# ESP_82661.net
KiCad netlist of a schematic drawn in Altium Designer
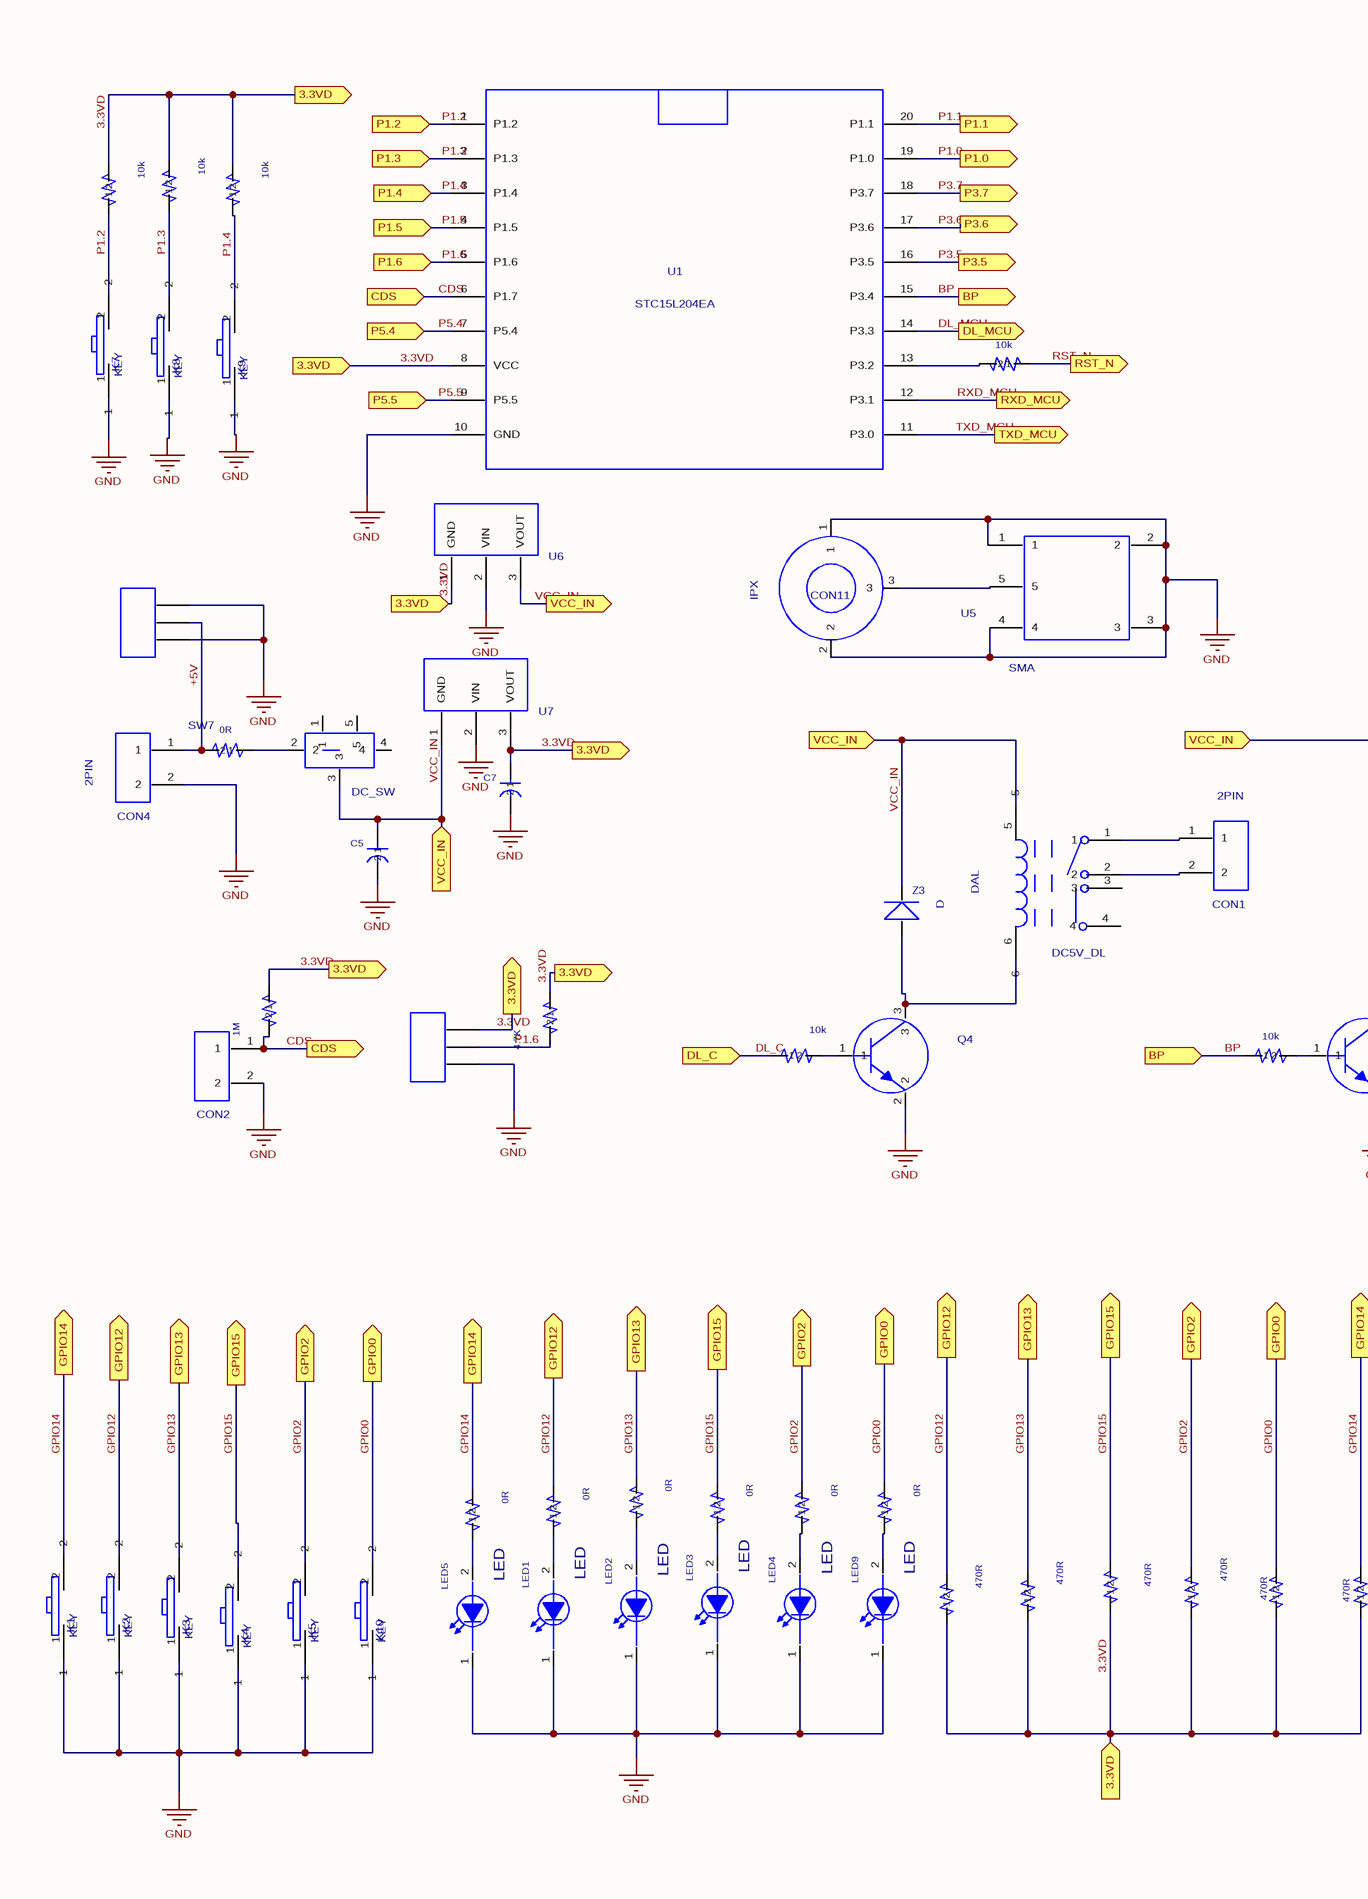
[diagram p0: ESP_82661.SchDoc, left]
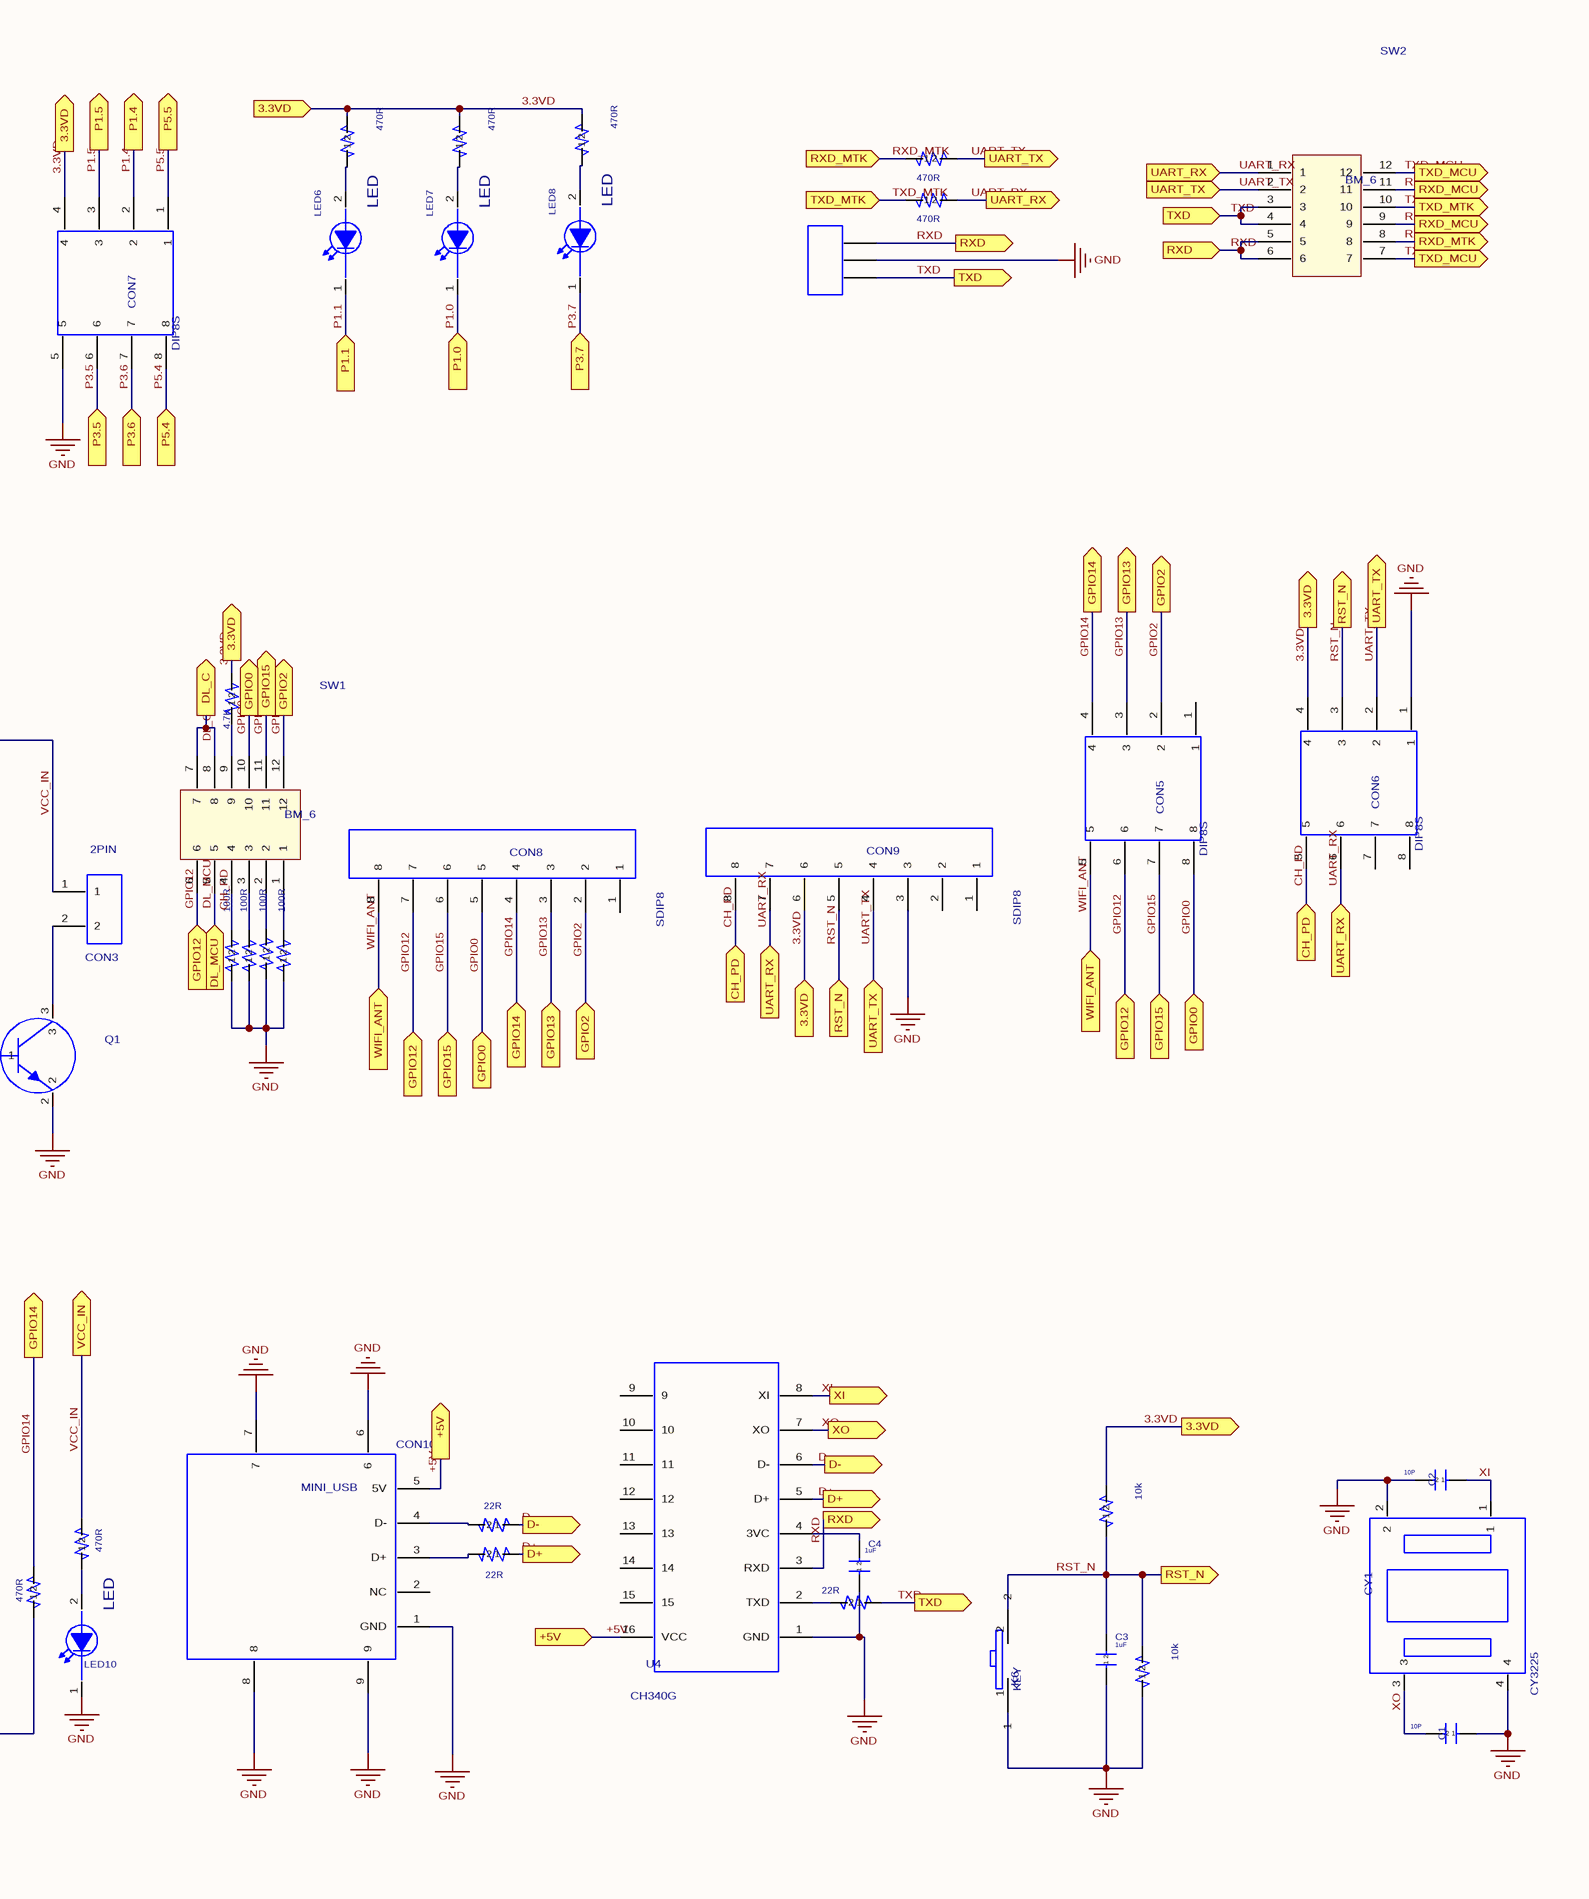
[diagram p1: ESP_82661.SchDoc, right]

(export (version "E")
  (design (tool "Eeschema 10.0.6"))
  (components
    (comp (ref "C1")
      (value "10P")
      (footprint "C0805/0603")
      (fields (field (name "Comment") "CAP"))
      (libsource (lib "*") (part "CAP"))
    )
    (comp (ref "C2")
      (value "10P")
      (footprint "C0805/0603")
      (fields (field (name "Comment") "CAP"))
      (libsource (lib "*") (part "CAP"))
    )
    (comp (ref "C3")
      (value "1uF")
      (footprint "C0805/0603")
      (fields (field (name "Comment") "CAP"))
      (libsource (lib "*") (part "CAP"))
    )
    (comp (ref "C4")
      (value "1uF")
      (footprint "C0805/0603")
      (fields (field (name "Comment") "CAP"))
      (libsource (lib "*") (part "CAP"))
    )
    (comp (ref "C5") (value "ECAP") (footprint "EC-10") (libsource (lib "*") (part "ECAP")))
    (comp (ref "C7") (value "ECAP") (footprint "EC") (libsource (lib "*") (part "ECAP")))
    (comp (ref "CON1") (value "2PIN") (footprint "AC2P") (libsource (lib "*") (part "2PIN")))
    (comp (ref "CON2") (value "2PIN") (footprint "2PIN") (libsource (lib "*") (part "2PIN")))
    (comp (ref "CON3") (value "2PIN") (footprint "BEEP") (libsource (lib "*") (part "2PIN")))
    (comp (ref "CON4") (value "2PIN") (footprint "2PIN") (libsource (lib "*") (part "2PIN")))
    (comp (ref "CON5") (value "DIP8S") (footprint "DIP8") (libsource (lib "*") (part "DIP8S")))
    (comp (ref "CON6") (value "DIP8S") (footprint "DIP8") (libsource (lib "*") (part "DIP8S")))
    (comp (ref "CON7") (value "DIP8S") (footprint "DIP8") (libsource (lib "*") (part "DIP8S")))
    (comp (ref "CON8") (value "SDIP8") (footprint "SDIP8") (libsource (lib "*") (part "SDIP8")))
    (comp (ref "CON9") (value "SDIP8") (footprint "SDIP8") (libsource (lib "*") (part "SDIP8")))
    (comp (ref "CON10") (value "MINI_USB") (footprint "MINUSB") (libsource (lib "*") (part "MINI_USB")))
    (comp (ref "CON11") (value "IPX") (footprint "IPX") (libsource (lib "*") (part "IPX")))
    (comp (ref "CY1")
      (value "CY3225")
      (footprint "CRYS/SMD/2.0X2.5/CXA-04000-2F3F40")
      (libsource (lib "*") (part "CY3225"))
    )
    (comp (ref "DC5V_DL") (value "DAL") (footprint "JDQ") (libsource (lib "*") (part "DAL")))
    (comp (ref "K1") (value "KEY") (footprint "QCKG") (libsource (lib "*") (part "KEY")))
    (comp (ref "K2") (value "KEY") (footprint "QCKG") (libsource (lib "*") (part "KEY")))
    (comp (ref "K3") (value "KEY") (footprint "QCKG") (libsource (lib "*") (part "KEY")))
    (comp (ref "K4") (value "KEY") (footprint "QCKG") (libsource (lib "*") (part "KEY")))
    (comp (ref "K5") (value "KEY") (footprint "QCKG") (libsource (lib "*") (part "KEY")))
    (comp (ref "K6") (value "KEY") (footprint "QCKG") (libsource (lib "*") (part "KEY")))
    (comp (ref "K7") (value "KEY") (footprint "QCKG") (libsource (lib "*") (part "KEY")))
    (comp (ref "K8") (value "KEY") (footprint "QCKG") (libsource (lib "*") (part "KEY")))
    (comp (ref "K9") (value "KEY") (footprint "QCKG") (libsource (lib "*") (part "KEY")))
    (comp (ref "K10") (value "KEY") (footprint "QCKG") (libsource (lib "*") (part "KEY")))
    (comp (ref "LED1") (value "LED") (footprint "0603") (libsource (lib "*") (part "LED")))
    (comp (ref "LED2") (value "LED") (footprint "0603") (libsource (lib "*") (part "LED")))
    (comp (ref "LED3") (value "LED") (footprint "0603") (libsource (lib "*") (part "LED")))
    (comp (ref "LED4") (value "LED") (footprint "0603") (libsource (lib "*") (part "LED")))
    (comp (ref "LED5") (value "LED") (footprint "0603") (libsource (lib "*") (part "LED")))
    (comp (ref "LED6") (value "LED") (footprint "0603") (libsource (lib "*") (part "LED")))
    (comp (ref "LED7") (value "LED") (footprint "0603") (libsource (lib "*") (part "LED")))
    (comp (ref "LED8") (value "LED") (footprint "0603") (libsource (lib "*") (part "LED")))
    (comp (ref "LED9") (value "LED") (footprint "0603") (libsource (lib "*") (part "LED")))
    (comp (ref "LED10") (value "LED") (footprint "0603") (libsource (lib "*") (part "LED")))
    (comp (ref "Q1")
      (value "2N3904")
      (footprint "SOT23")
      (description "SOT23")
      (libsource (lib "*") (part "2N3904"))
    )
    (comp (ref "Q4")
      (value "2N3904")
      (footprint "SOT23")
      (description "SOT23")
      (libsource (lib "*") (part "2N3904"))
    )
    (comp (ref "R1")
      (value "470R")
      (footprint "R0805/0603")
      (fields (field (name "Comment") "RES"))
      (libsource (lib "*") (part "RES"))
    )
    (comp (ref "R2")
      (value "0R")
      (footprint "R0805/0603")
      (fields (field (name "Comment") "RES"))
      (libsource (lib "*") (part "RES"))
    )
    (comp (ref "R3")
      (value "0R")
      (footprint "R0805/0603")
      (fields (field (name "Comment") "RES"))
      (libsource (lib "*") (part "RES"))
    )
    (comp (ref "R4")
      (value "0R")
      (footprint "R0805/0603")
      (fields (field (name "Comment") "RES"))
      (libsource (lib "*") (part "RES"))
    )
    (comp (ref "R5")
      (value "470R")
      (footprint "R0805/0603")
      (fields (field (name "Comment") "RES"))
      (libsource (lib "*") (part "RES"))
    )
    (comp (ref "R6")
      (value "0R")
      (footprint "R0805/0603")
      (fields (field (name "Comment") "RES"))
      (libsource (lib "*") (part "RES"))
    )
    (comp (ref "R7")
      (value "0R")
      (footprint "R0805/0603")
      (fields (field (name "Comment") "RES"))
      (libsource (lib "*") (part "RES"))
    )
    (comp (ref "R8")
      (value "470R")
      (footprint "R0805/0603")
      (fields (field (name "Comment") "RES"))
      (libsource (lib "*") (part "RES"))
    )
    (comp (ref "R9")
      (value "470R")
      (footprint "R0805/0603")
      (fields (field (name "Comment") "RES"))
      (libsource (lib "*") (part "RES"))
    )
    (comp (ref "R10")
      (value "470R")
      (footprint "R0805/0603")
      (fields (field (name "Comment") "RES"))
      (libsource (lib "*") (part "RES"))
    )
    (comp (ref "R11")
      (value "470R")
      (footprint "R0805/0603")
      (fields (field (name "Comment") "RES"))
      (libsource (lib "*") (part "RES"))
    )
    (comp (ref "R12")
      (value "470R")
      (footprint "R0805/0603")
      (fields (field (name "Comment") "RES"))
      (libsource (lib "*") (part "RES"))
    )
    (comp (ref "R13")
      (value "10k")
      (footprint "R0805/0603")
      (fields (field (name "Comment") "RES"))
      (libsource (lib "*") (part "RES"))
    )
    (comp (ref "R14")
      (value "10k")
      (footprint "R0805/0603")
      (fields (field (name "Comment") "RES"))
      (libsource (lib "*") (part "RES"))
    )
    (comp (ref "R15")
      (value "470R")
      (footprint "R0805/0603")
      (fields (field (name "Comment") "RES"))
      (libsource (lib "*") (part "RES"))
    )
    (comp (ref "R16")
      (value "22R")
      (footprint "R0805/0603")
      (fields (field (name "Comment") "RES"))
      (libsource (lib "*") (part "RES"))
    )
    (comp (ref "R17")
      (value "22R")
      (footprint "R0805/0603")
      (fields (field (name "Comment") "RES"))
      (libsource (lib "*") (part "RES"))
    )
    (comp (ref "R18")
      (value "22R")
      (footprint "R0805/0603")
      (fields (field (name "Comment") "RES"))
      (libsource (lib "*") (part "RES"))
    )
    (comp (ref "R19")
      (value "10k")
      (footprint "R0805/0603")
      (fields (field (name "Comment") "RES"))
      (libsource (lib "*") (part "RES"))
    )
    (comp (ref "R20")
      (value "0R")
      (footprint "R0805/0603")
      (fields (field (name "Comment") "RES"))
      (libsource (lib "*") (part "RES"))
    )
    (comp (ref "R21")
      (value "1M")
      (footprint "R0805/0603")
      (fields (field (name "Comment") "RES"))
      (libsource (lib "*") (part "RES"))
    )
    (comp (ref "R22")
      (value "10k")
      (footprint "R0805/0603")
      (fields (field (name "Comment") "RES"))
      (libsource (lib "*") (part "RES"))
    )
    (comp (ref "R23")
      (value "10k")
      (footprint "R0805/0603")
      (fields (field (name "Comment") "RES"))
      (libsource (lib "*") (part "RES"))
    )
    (comp (ref "R24")
      (value "0R")
      (footprint "R0805/0603")
      (fields (field (name "Comment") "RES"))
      (libsource (lib "*") (part "RES"))
    )
    (comp (ref "R25")
      (value "470R")
      (footprint "R0805/0603")
      (fields (field (name "Comment") "RES"))
      (libsource (lib "*") (part "RES"))
    )
    (comp (ref "R26")
      (value "470R")
      (footprint "R0805/0603")
      (fields (field (name "Comment") "RES"))
      (libsource (lib "*") (part "RES"))
    )
    (comp (ref "R27")
      (value "470R")
      (footprint "R0805/0603")
      (fields (field (name "Comment") "RES"))
      (libsource (lib "*") (part "RES"))
    )
    (comp (ref "R28")
      (value "470R")
      (footprint "R0805/0603")
      (fields (field (name "Comment") "RES"))
      (libsource (lib "*") (part "RES"))
    )
    (comp (ref "R29")
      (value "10k")
      (footprint "R0805/0603")
      (fields (field (name "Comment") "RES"))
      (libsource (lib "*") (part "RES"))
    )
    (comp (ref "R30")
      (value "10k")
      (footprint "R0805/0603")
      (fields (field (name "Comment") "RES"))
      (libsource (lib "*") (part "RES"))
    )
    (comp (ref "R31")
      (value "10k")
      (footprint "R0805/0603")
      (fields (field (name "Comment") "RES"))
      (libsource (lib "*") (part "RES"))
    )
    (comp (ref "R32")
      (value "100R")
      (footprint "R0805/0603")
      (fields (field (name "Comment") "RES"))
      (libsource (lib "*") (part "RES"))
    )
    (comp (ref "R33")
      (value "100R")
      (footprint "R0805/0603")
      (fields (field (name "Comment") "RES"))
      (libsource (lib "*") (part "RES"))
    )
    (comp (ref "R34")
      (value "100R")
      (footprint "R0805/0603")
      (fields (field (name "Comment") "RES"))
      (libsource (lib "*") (part "RES"))
    )
    (comp (ref "R35")
      (value "100R")
      (footprint "R0805/0603")
      (fields (field (name "Comment") "RES"))
      (libsource (lib "*") (part "RES"))
    )
    (comp (ref "R37")
      (value "4.7K")
      (footprint "R0805/0603")
      (fields (field (name "Comment") "RES"))
      (libsource (lib "*") (part "RES"))
    )
    (comp (ref "R38")
      (value "4.7K")
      (footprint "R0805/0603")
      (fields (field (name "Comment") "RES"))
      (libsource (lib "*") (part "RES"))
    )
    (comp (ref "SW1") (value "BM_6") (footprint "BM_6_DEC") (libsource (lib "ESP_8266") (part "BM_6")))
    (comp (ref "SW2") (value "BM_6") (footprint "BM_6_DEC") (libsource (lib "ESP_8266") (part "BM_6")))
    (comp (ref "SW7") (value "DC_SW") (footprint "DC_SW") (libsource (lib "*") (part "DC_SW")))
    (comp (ref "U1") (value "STC15L204EA") (footprint "SOP20") (libsource (lib "*") (part "STC15L204EA")))
    (comp (ref "U2") (value "3PIN") (footprint "3PIN") (libsource (lib "*") (part "3PIN")))
    (comp (ref "U3") (value "3PIN") (footprint "DC_CON8") (libsource (lib "*") (part "3PIN")))
    (comp (ref "U4") (value "CH340G") (footprint "SO16MB") (libsource (lib "*") (part "CH340G")))
    (comp (ref "U5") (value "SMA") (footprint "SMA") (libsource (lib "*") (part "SMA")))
    (comp (ref "U6") (value "HT71XX") (footprint "SOT223") (libsource (lib "*") (part "HT71XX")))
    (comp (ref "U7") (value "HT71XX") (footprint "SOT89") (libsource (lib "*") (part "HT71XX")))
    (comp (ref "U8") (value "3PIN") (footprint "3PIN") (libsource (lib "*") (part "3PIN")))
    (comp (ref "Z3") (value "D") (footprint "DIDO-1") (libsource (lib "*") (part "D")))
  )
  (nets
    (net (code "1") (name "/+5V") (class "Default")
      (node (ref "CON10") (pin "5") (pinfunction "5V_5") (pintype "passive"))
      (node (ref "CON4") (pin "1") (pinfunction "1_1") (pintype "passive"))
      (node (ref "R24") (pin "1") (pinfunction "1_1") (pintype "passive"))
      (node (ref "U3") (pin "2") (pinfunction "2_2") (pintype "passive"))
      (node (ref "U4") (pin "16") (pinfunction "VCC_16") (pintype "passive"))
    )
    (net (code "2") (name "/3.3VD") (class "Default")
      (node (ref "C7") (pin "2") (pinfunction "2_2") (pintype "passive"))
      (node (ref "CON6") (pin "4") (pinfunction "4_4") (pintype "passive"))
      (node (ref "CON7") (pin "4") (pinfunction "4_4") (pintype "passive"))
      (node (ref "CON9") (pin "6") (pinfunction "6_6") (pintype "passive"))
      (node (ref "R10") (pin "2") (pinfunction "2_2") (pintype "passive"))
      (node (ref "R11") (pin "2") (pinfunction "2_2") (pintype "passive"))
      (node (ref "R12") (pin "2") (pinfunction "2_2") (pintype "passive"))
      (node (ref "R13") (pin "1") (pinfunction "1_1") (pintype "passive"))
      (node (ref "R21") (pin "2") (pinfunction "2_2") (pintype "passive"))
      (node (ref "R25") (pin "1") (pinfunction "1_1") (pintype "passive"))
      (node (ref "R26") (pin "1") (pinfunction "1_1") (pintype "passive"))
      (node (ref "R27") (pin "1") (pinfunction "1_1") (pintype "passive"))
      (node (ref "R28") (pin "2") (pinfunction "2_2") (pintype "passive"))
      (node (ref "R29") (pin "1") (pinfunction "1_1") (pintype "passive"))
      (node (ref "R30") (pin "1") (pinfunction "1_1") (pintype "passive"))
      (node (ref "R31") (pin "1") (pinfunction "1_1") (pintype "passive"))
      (node (ref "R37") (pin "2") (pinfunction "2_2") (pintype "passive"))
      (node (ref "R38") (pin "1") (pinfunction "1_1") (pintype "passive"))
      (node (ref "R8") (pin "2") (pinfunction "2_2") (pintype "passive"))
      (node (ref "R9") (pin "2") (pinfunction "2_2") (pintype "passive"))
      (node (ref "U1") (pin "8") (pinfunction "VCC_8") (pintype "passive"))
      (node (ref "U6") (pin "1") (pinfunction "GND_1") (pintype "passive"))
      (node (ref "U7") (pin "3") (pinfunction "VOUT_3") (pintype "passive"))
      (node (ref "U8") (pin "1") (pinfunction "1_1") (pintype "passive"))
    )
    (net (code "3") (name "/BP") (class "Default")
      (node (ref "R23") (pin "2") (pinfunction "2_2") (pintype "passive"))
      (node (ref "U1") (pin "15") (pinfunction "P3.4_15") (pintype "passive"))
    )
    (net (code "4") (name "/CDS") (class "Default")
      (node (ref "CON2") (pin "1") (pinfunction "1_1") (pintype "passive"))
      (node (ref "R21") (pin "1") (pinfunction "1_1") (pintype "passive"))
      (node (ref "U1") (pin "6") (pinfunction "P1.7_6") (pintype "passive"))
    )
    (net (code "5") (name "/CH_PD") (class "Default")
      (node (ref "CON6") (pin "5") (pinfunction "5_5") (pintype "passive"))
      (node (ref "CON9") (pin "8") (pinfunction "8_8") (pintype "passive"))
      (node (ref "R35") (pin "1") (pinfunction "1_1") (pintype "passive"))
      (node (ref "SW1") (pin "4") (pinfunction "4_4") (pintype "passive"))
    )
    (net (code "6") (name "/D+") (class "Default")
      (node (ref "R17") (pin "2") (pinfunction "2_2") (pintype "passive"))
      (node (ref "U4") (pin "5") (pinfunction "D+_5") (pintype "passive"))
    )
    (net (code "7") (name "/D-") (class "Default")
      (node (ref "R16") (pin "2") (pinfunction "2_2") (pintype "passive"))
      (node (ref "U4") (pin "6") (pinfunction "D-_6") (pintype "passive"))
    )
    (net (code "8") (name "/DL_C") (class "Default")
      (node (ref "R22") (pin "2") (pinfunction "2_2") (pintype "passive"))
      (node (ref "SW1") (pin "7") (pinfunction "7_7") (pintype "passive"))
      (node (ref "SW1") (pin "8") (pinfunction "8_8") (pintype "passive"))
    )
    (net (code "9") (name "/DL_MCU") (class "Default")
      (node (ref "SW1") (pin "5") (pinfunction "5_5") (pintype "passive"))
      (node (ref "U1") (pin "14") (pinfunction "P3.3_14") (pintype "passive"))
    )
    (net (code "10") (name "/GPIO0") (class "Default")
      (node (ref "CON5") (pin "8") (pinfunction "8_8") (pintype "passive"))
      (node (ref "CON8") (pin "5") (pinfunction "5_5") (pintype "passive"))
      (node (ref "R12") (pin "1") (pinfunction "1_1") (pintype "passive"))
      (node (ref "R20") (pin "1") (pinfunction "1_1") (pintype "passive"))
      (node (ref "SW1") (pin "10") (pinfunction "10_10") (pintype "passive"))
    )
    (net (code "11") (name "/GPIO2") (class "Default")
      (node (ref "CON5") (pin "2") (pinfunction "2_2") (pintype "passive"))
      (node (ref "CON8") (pin "2") (pinfunction "2_2") (pintype "passive"))
      (node (ref "R11") (pin "1") (pinfunction "1_1") (pintype "passive"))
      (node (ref "R7") (pin "1") (pinfunction "1_1") (pintype "passive"))
      (node (ref "SW1") (pin "12") (pinfunction "12_12") (pintype "passive"))
    )
    (net (code "12") (name "/GPIO12") (class "Default")
      (node (ref "CON5") (pin "6") (pinfunction "6_6") (pintype "passive"))
      (node (ref "CON8") (pin "7") (pinfunction "7_7") (pintype "passive"))
      (node (ref "R3") (pin "1") (pinfunction "1_1") (pintype "passive"))
      (node (ref "R8") (pin "1") (pinfunction "1_1") (pintype "passive"))
      (node (ref "SW1") (pin "6") (pinfunction "6_6") (pintype "passive"))
    )
    (net (code "13") (name "/GPIO13") (class "Default")
      (node (ref "CON5") (pin "3") (pinfunction "3_3") (pintype "passive"))
      (node (ref "CON8") (pin "3") (pinfunction "3_3") (pintype "passive"))
      (node (ref "R4") (pin "1") (pinfunction "1_1") (pintype "passive"))
      (node (ref "R9") (pin "1") (pinfunction "1_1") (pintype "passive"))
    )
    (net (code "14") (name "/GPIO14") (class "Default")
      (node (ref "CON5") (pin "4") (pinfunction "4_4") (pintype "passive"))
      (node (ref "CON8") (pin "4") (pinfunction "4_4") (pintype "passive"))
      (node (ref "R2") (pin "1") (pinfunction "1_1") (pintype "passive"))
      (node (ref "R28") (pin "1") (pinfunction "1_1") (pintype "passive"))
    )
    (net (code "15") (name "/GPIO15") (class "Default")
      (node (ref "CON5") (pin "7") (pinfunction "7_7") (pintype "passive"))
      (node (ref "CON8") (pin "6") (pinfunction "6_6") (pintype "passive"))
      (node (ref "R10") (pin "1") (pinfunction "1_1") (pintype "passive"))
      (node (ref "R6") (pin "1") (pinfunction "1_1") (pintype "passive"))
      (node (ref "SW1") (pin "11") (pinfunction "11_11") (pintype "passive"))
    )
    (net (code "16") (name "/P1.0") (class "Default")
      (node (ref "LED7") (pin "1") (pinfunction "CATHODE_1") (pintype "passive"))
      (node (ref "U1") (pin "19") (pinfunction "P1.0_19") (pintype "passive"))
    )
    (net (code "17") (name "/P1.1") (class "Default")
      (node (ref "LED6") (pin "1") (pinfunction "CATHODE_1") (pintype "passive"))
      (node (ref "U1") (pin "20") (pinfunction "P1.1_20") (pintype "passive"))
    )
    (net (code "18") (name "/P1.2") (class "Default")
      (node (ref "R29") (pin "2") (pinfunction "2_2") (pintype "passive"))
      (node (ref "U1") (pin "1") (pinfunction "P1.2_1") (pintype "passive"))
    )
    (net (code "19") (name "/P1.3") (class "Default")
      (node (ref "R30") (pin "2") (pinfunction "2_2") (pintype "passive"))
      (node (ref "U1") (pin "2") (pinfunction "P1.3_2") (pintype "passive"))
    )
    (net (code "20") (name "/P1.4") (class "Default")
      (node (ref "CON7") (pin "2") (pinfunction "2_2") (pintype "passive"))
      (node (ref "R31") (pin "2") (pinfunction "2_2") (pintype "passive"))
      (node (ref "U1") (pin "3") (pinfunction "P1.4_3") (pintype "passive"))
    )
    (net (code "21") (name "/P1.5") (class "Default")
      (node (ref "CON7") (pin "3") (pinfunction "3_3") (pintype "passive"))
      (node (ref "U1") (pin "4") (pinfunction "P1.5_4") (pintype "passive"))
    )
    (net (code "22") (name "/P1.6") (class "Default")
      (node (ref "R37") (pin "1") (pinfunction "1_1") (pintype "passive"))
      (node (ref "U1") (pin "5") (pinfunction "P1.6_5") (pintype "passive"))
      (node (ref "U8") (pin "2") (pinfunction "2_2") (pintype "passive"))
    )
    (net (code "23") (name "/P3.5") (class "Default")
      (node (ref "CON7") (pin "6") (pinfunction "6_6") (pintype "passive"))
      (node (ref "U1") (pin "16") (pinfunction "P3.5_16") (pintype "passive"))
    )
    (net (code "24") (name "/P3.6") (class "Default")
      (node (ref "CON7") (pin "7") (pinfunction "7_7") (pintype "passive"))
      (node (ref "U1") (pin "17") (pinfunction "P3.6_17") (pintype "passive"))
    )
    (net (code "25") (name "/P3.7") (class "Default")
      (node (ref "LED8") (pin "1") (pinfunction "CATHODE_1") (pintype "passive"))
      (node (ref "U1") (pin "18") (pinfunction "P3.7_18") (pintype "passive"))
    )
    (net (code "26") (name "/P5.4") (class "Default")
      (node (ref "CON7") (pin "8") (pinfunction "8_8") (pintype "passive"))
      (node (ref "U1") (pin "7") (pinfunction "P5.4_7") (pintype "passive"))
    )
    (net (code "27") (name "/P5.5") (class "Default")
      (node (ref "CON7") (pin "1") (pinfunction "1_1") (pintype "passive"))
      (node (ref "U1") (pin "9") (pinfunction "P5.5_9") (pintype "passive"))
    )
    (net (code "28") (name "/RST_N") (class "Default")
      (node (ref "C3") (pin "1") (pinfunction "1_1") (pintype "passive"))
      (node (ref "CON6") (pin "3") (pinfunction "3_3") (pintype "passive"))
      (node (ref "CON9") (pin "5") (pinfunction "5_5") (pintype "passive"))
      (node (ref "R13") (pin "2") (pinfunction "2_2") (pintype "passive"))
      (node (ref "R14") (pin "2") (pinfunction "2_2") (pintype "passive"))
      (node (ref "R19") (pin "1") (pinfunction "1_1") (pintype "passive"))
    )
    (net (code "29") (name "/RXD") (class "Default")
      (node (ref "SW2") (pin "5") (pinfunction "5_5") (pintype "passive"))
      (node (ref "SW2") (pin "6") (pinfunction "6_6") (pintype "passive"))
      (node (ref "U2") (pin "1") (pinfunction "1_1") (pintype "passive"))
      (node (ref "U4") (pin "3") (pinfunction "RXD_3") (pintype "passive"))
    )
    (net (code "30") (name "/RXD_MCU") (class "Default")
      (node (ref "SW2") (pin "11") (pinfunction "11_11") (pintype "passive"))
      (node (ref "SW2") (pin "9") (pinfunction "9_9") (pintype "passive"))
      (node (ref "U1") (pin "12") (pinfunction "P3.1_12") (pintype "passive"))
    )
    (net (code "31") (name "/RXD_MTK") (class "Default")
      (node (ref "R5") (pin "2") (pinfunction "2_2") (pintype "passive"))
      (node (ref "SW2") (pin "8") (pinfunction "8_8") (pintype "passive"))
    )
    (net (code "32") (name "/TXD") (class "Default")
      (node (ref "R18") (pin "2") (pinfunction "2_2") (pintype "passive"))
      (node (ref "SW2") (pin "3") (pinfunction "3_3") (pintype "passive"))
      (node (ref "SW2") (pin "4") (pinfunction "4_4") (pintype "passive"))
      (node (ref "U2") (pin "3") (pinfunction "3_3") (pintype "passive"))
    )
    (net (code "33") (name "/TXD_MCU") (class "Default")
      (node (ref "SW2") (pin "12") (pinfunction "12_12") (pintype "passive"))
      (node (ref "SW2") (pin "7") (pinfunction "7_7") (pintype "passive"))
      (node (ref "U1") (pin "11") (pinfunction "P3.0_11") (pintype "passive"))
    )
    (net (code "34") (name "/TXD_MTK") (class "Default")
      (node (ref "R1") (pin "2") (pinfunction "2_2") (pintype "passive"))
      (node (ref "SW2") (pin "10") (pinfunction "10_10") (pintype "passive"))
    )
    (net (code "35") (name "/UART_RX") (class "Default")
      (node (ref "CON6") (pin "6") (pinfunction "6_6") (pintype "passive"))
      (node (ref "CON9") (pin "7") (pinfunction "7_7") (pintype "passive"))
      (node (ref "R1") (pin "1") (pinfunction "1_1") (pintype "passive"))
      (node (ref "SW2") (pin "1") (pinfunction "1_1") (pintype "passive"))
    )
    (net (code "36") (name "/UART_TX") (class "Default")
      (node (ref "CON6") (pin "2") (pinfunction "2_2") (pintype "passive"))
      (node (ref "CON9") (pin "4") (pinfunction "4_4") (pintype "passive"))
      (node (ref "R5") (pin "1") (pinfunction "1_1") (pintype "passive"))
      (node (ref "SW2") (pin "2") (pinfunction "2_2") (pintype "passive"))
    )
    (net (code "37") (name "/VCC_IN") (class "Default")
      (node (ref "C5") (pin "2") (pinfunction "2_2") (pintype "passive"))
      (node (ref "CON3") (pin "1") (pinfunction "1_1") (pintype "passive"))
      (node (ref "R15") (pin "1") (pinfunction "1_1") (pintype "passive"))
      (node (ref "SW7") (pin "3") (pinfunction "3_3") (pintype "passive"))
      (node (ref "U6") (pin "3") (pinfunction "VOUT_3") (pintype "passive"))
      (node (ref "U7") (pin "1") (pinfunction "GND_1") (pintype "passive"))
      (node (ref "Z3") (pin "2") (pinfunction "2_2") (pintype "passive"))
    )
    (net (code "38") (name "/WIFI_ANT") (class "Default")
      (node (ref "CON5") (pin "5") (pinfunction "5_5") (pintype "passive"))
      (node (ref "CON8") (pin "8") (pinfunction "8_8") (pintype "passive"))
    )
    (net (code "39") (name "/XI") (class "Default")
      (node (ref "C2") (pin "2") (pinfunction "2_2") (pintype "passive"))
      (node (ref "CY1") (pin "1") (pinfunction "1_1") (pintype "passive"))
      (node (ref "U4") (pin "8") (pinfunction "XI_8") (pintype "passive"))
    )
    (net (code "40") (name "/XO") (class "Default")
      (node (ref "C1") (pin "1") (pinfunction "1_1") (pintype "passive"))
      (node (ref "CY1") (pin "3") (pinfunction "3_3") (pintype "passive"))
      (node (ref "U4") (pin "7") (pinfunction "XO_7") (pintype "passive"))
    )
    (net (code "41") (name "GND") (class "Default")
      (node (ref "C1") (pin "2") (pinfunction "2_2") (pintype "passive"))
      (node (ref "C2") (pin "1") (pinfunction "1_1") (pintype "passive"))
      (node (ref "C3") (pin "2") (pinfunction "2_2") (pintype "passive"))
      (node (ref "C4") (pin "2") (pinfunction "2_2") (pintype "passive"))
      (node (ref "C5") (pin "1") (pinfunction "1_1") (pintype "passive"))
      (node (ref "C7") (pin "1") (pinfunction "1_1") (pintype "passive"))
      (node (ref "CON10") (pin "1") (pinfunction "GND_1") (pintype "passive"))
      (node (ref "CON10") (pin "6") (pinfunction "6_6") (pintype "passive"))
      (node (ref "CON10") (pin "7") (pinfunction "7_7") (pintype "passive"))
      (node (ref "CON10") (pin "8") (pinfunction "8_8") (pintype "passive"))
      (node (ref "CON10") (pin "9") (pinfunction "9_9") (pintype "passive"))
      (node (ref "CON11") (pin "1") (pinfunction "1_1") (pintype "passive"))
      (node (ref "CON11") (pin "2") (pinfunction "2_2") (pintype "passive"))
      (node (ref "CON2") (pin "2") (pinfunction "2_2") (pintype "passive"))
      (node (ref "CON4") (pin "2") (pinfunction "2_2") (pintype "passive"))
      (node (ref "CON6") (pin "1") (pinfunction "1_1") (pintype "passive"))
      (node (ref "CON7") (pin "5") (pinfunction "5_5") (pintype "passive"))
      (node (ref "CON9") (pin "3") (pinfunction "3_3") (pintype "passive"))
      (node (ref "CY1") (pin "2") (pinfunction "2_2") (pintype "passive"))
      (node (ref "CY1") (pin "4") (pinfunction "4_4") (pintype "passive"))
      (node (ref "LED1") (pin "1") (pinfunction "CATHODE_1") (pintype "passive"))
      (node (ref "LED10") (pin "1") (pinfunction "CATHODE_1") (pintype "passive"))
      (node (ref "LED2") (pin "1") (pinfunction "CATHODE_1") (pintype "passive"))
      (node (ref "LED3") (pin "1") (pinfunction "CATHODE_1") (pintype "passive"))
      (node (ref "LED4") (pin "1") (pinfunction "CATHODE_1") (pintype "passive"))
      (node (ref "LED5") (pin "1") (pinfunction "CATHODE_1") (pintype "passive"))
      (node (ref "LED9") (pin "1") (pinfunction "CATHODE_1") (pintype "passive"))
      (node (ref "Q1") (pin "2") (pinfunction "2_2") (pintype "passive"))
      (node (ref "Q4") (pin "2") (pinfunction "2_2") (pintype "passive"))
      (node (ref "R19") (pin "2") (pinfunction "2_2") (pintype "passive"))
      (node (ref "R32") (pin "2") (pinfunction "2_2") (pintype "passive"))
      (node (ref "R33") (pin "2") (pinfunction "2_2") (pintype "passive"))
      (node (ref "R34") (pin "2") (pinfunction "2_2") (pintype "passive"))
      (node (ref "R35") (pin "2") (pinfunction "2_2") (pintype "passive"))
      (node (ref "U1") (pin "10") (pinfunction "GND_10") (pintype "passive"))
      (node (ref "U2") (pin "2") (pinfunction "2_2") (pintype "passive"))
      (node (ref "U3") (pin "1") (pinfunction "1_1") (pintype "passive"))
      (node (ref "U3") (pin "3") (pinfunction "3_3") (pintype "passive"))
      (node (ref "U4") (pin "1") (pinfunction "GND_1") (pintype "passive"))
      (node (ref "U5") (pin "1") (pinfunction "1_1") (pintype "passive"))
      (node (ref "U5") (pin "2") (pinfunction "2_2") (pintype "passive"))
      (node (ref "U5") (pin "3") (pinfunction "3_3") (pintype "passive"))
      (node (ref "U5") (pin "4") (pinfunction "4_4") (pintype "passive"))
      (node (ref "U6") (pin "2") (pinfunction "VIN_2") (pintype "passive"))
      (node (ref "U7") (pin "2") (pinfunction "VIN_2") (pintype "passive"))
      (node (ref "U8") (pin "3") (pinfunction "3_3") (pintype "passive"))
    )
    (net (code "42") (name "Net-(CON1-Pad1)") (class "Default")
      (node (ref "CON1") (pin "1") (pinfunction "1_1") (pintype "passive"))
      (node (ref "DC5V_DL") (pin "1") (pinfunction "1_1") (pintype "passive"))
    )
    (net (code "43") (name "Net-(CON1-Pad2)") (class "Default")
      (node (ref "CON1") (pin "2") (pinfunction "2_2") (pintype "passive"))
      (node (ref "DC5V_DL") (pin "2") (pinfunction "2_2") (pintype "passive"))
    )
    (net (code "44") (name "Net-(CON3-Pad2)") (class "Default")
      (node (ref "CON3") (pin "2") (pinfunction "2_2") (pintype "passive"))
      (node (ref "Q1") (pin "3") (pinfunction "3_3") (pintype "passive"))
    )
    (net (code "45") (name "Net-(CON10-D+)") (class "Default")
      (node (ref "CON10") (pin "3") (pinfunction "D+_3") (pintype "passive"))
      (node (ref "R17") (pin "1") (pinfunction "1_1") (pintype "passive"))
    )
    (net (code "46") (name "Net-(CON10-D-)") (class "Default")
      (node (ref "CON10") (pin "4") (pinfunction "D-_4") (pintype "passive"))
      (node (ref "R16") (pin "1") (pinfunction "1_1") (pintype "passive"))
    )
    (net (code "47") (name "Net-(CON11-Pad3)") (class "Default")
      (node (ref "CON11") (pin "3") (pinfunction "3_3") (pintype "passive"))
      (node (ref "U5") (pin "5") (pinfunction "5_5") (pintype "passive"))
    )
    (net (code "48") (name "Net-(LED1-ANODE)") (class "Default")
      (node (ref "LED1") (pin "2") (pinfunction "ANODE_2") (pintype "passive"))
      (node (ref "R3") (pin "2") (pinfunction "2_2") (pintype "passive"))
    )
    (net (code "49") (name "Net-(LED2-ANODE)") (class "Default")
      (node (ref "LED2") (pin "2") (pinfunction "ANODE_2") (pintype "passive"))
      (node (ref "R4") (pin "2") (pinfunction "2_2") (pintype "passive"))
    )
    (net (code "50") (name "Net-(LED3-ANODE)") (class "Default")
      (node (ref "LED3") (pin "2") (pinfunction "ANODE_2") (pintype "passive"))
      (node (ref "R6") (pin "2") (pinfunction "2_2") (pintype "passive"))
    )
    (net (code "51") (name "Net-(LED4-ANODE)") (class "Default")
      (node (ref "LED4") (pin "2") (pinfunction "ANODE_2") (pintype "passive"))
      (node (ref "R7") (pin "2") (pinfunction "2_2") (pintype "passive"))
    )
    (net (code "52") (name "Net-(LED5-ANODE)") (class "Default")
      (node (ref "LED5") (pin "2") (pinfunction "ANODE_2") (pintype "passive"))
      (node (ref "R2") (pin "2") (pinfunction "2_2") (pintype "passive"))
    )
    (net (code "53") (name "Net-(LED6-ANODE)") (class "Default")
      (node (ref "LED6") (pin "2") (pinfunction "ANODE_2") (pintype "passive"))
      (node (ref "R25") (pin "2") (pinfunction "2_2") (pintype "passive"))
    )
    (net (code "54") (name "Net-(LED7-ANODE)") (class "Default")
      (node (ref "LED7") (pin "2") (pinfunction "ANODE_2") (pintype "passive"))
      (node (ref "R26") (pin "2") (pinfunction "2_2") (pintype "passive"))
    )
    (net (code "55") (name "Net-(LED8-ANODE)") (class "Default")
      (node (ref "LED8") (pin "2") (pinfunction "ANODE_2") (pintype "passive"))
      (node (ref "R27") (pin "2") (pinfunction "2_2") (pintype "passive"))
    )
    (net (code "56") (name "Net-(LED9-ANODE)") (class "Default")
      (node (ref "LED9") (pin "2") (pinfunction "ANODE_2") (pintype "passive"))
      (node (ref "R20") (pin "2") (pinfunction "2_2") (pintype "passive"))
    )
    (net (code "57") (name "Net-(LED10-ANODE)") (class "Default")
      (node (ref "LED10") (pin "2") (pinfunction "ANODE_2") (pintype "passive"))
      (node (ref "R15") (pin "2") (pinfunction "2_2") (pintype "passive"))
    )
    (net (code "58") (name "Net-(Q1-Pad1)") (class "Default")
      (node (ref "Q1") (pin "1") (pinfunction "1_1") (pintype "passive"))
      (node (ref "R23") (pin "1") (pinfunction "1_1") (pintype "passive"))
    )
    (net (code "59") (name "Net-(Q4-Pad1)") (class "Default")
      (node (ref "Q4") (pin "1") (pinfunction "1_1") (pintype "passive"))
      (node (ref "R22") (pin "1") (pinfunction "1_1") (pintype "passive"))
    )
    (net (code "60") (name "Net-(Q4-Pad3)") (class "Default")
      (node (ref "Q4") (pin "3") (pinfunction "3_3") (pintype "passive"))
      (node (ref "Z3") (pin "1") (pinfunction "1_1") (pintype "passive"))
    )
    (net (code "61") (name "Net-(R24-Pad2)") (class "Default")
      (node (ref "R24") (pin "2") (pinfunction "2_2") (pintype "passive"))
      (node (ref "SW7") (pin "2") (pinfunction "2_2") (pintype "passive"))
    )
    (net (code "62") (name "Net-(R32-Pad1)") (class "Default")
      (node (ref "R32") (pin "1") (pinfunction "1_1") (pintype "passive"))
      (node (ref "SW1") (pin "1") (pinfunction "1_1") (pintype "passive"))
    )
    (net (code "63") (name "Net-(R33-Pad1)") (class "Default")
      (node (ref "R33") (pin "1") (pinfunction "1_1") (pintype "passive"))
      (node (ref "SW1") (pin "2") (pinfunction "2_2") (pintype "passive"))
    )
    (net (code "64") (name "Net-(R34-Pad1)") (class "Default")
      (node (ref "R34") (pin "1") (pinfunction "1_1") (pintype "passive"))
      (node (ref "SW1") (pin "3") (pinfunction "3_3") (pintype "passive"))
    )
    (net (code "65") (name "Net-(R38-Pad2)") (class "Default")
      (node (ref "R38") (pin "2") (pinfunction "2_2") (pintype "passive"))
      (node (ref "SW1") (pin "9") (pinfunction "9_9") (pintype "passive"))
    )
    (net (code "66") (name "Net-(U1-P3.2)") (class "Default")
      (node (ref "R14") (pin "1") (pinfunction "1_1") (pintype "passive"))
      (node (ref "U1") (pin "13") (pinfunction "P3.2_13") (pintype "passive"))
    )
    (net (code "67") (name "Net-(U4-3VC)") (class "Default")
      (node (ref "C4") (pin "1") (pinfunction "1_1") (pintype "passive"))
      (node (ref "U4") (pin "4") (pinfunction "3VC_4") (pintype "passive"))
    )
    (net (code "68") (name "Net-(U4-TXD)") (class "Default")
      (node (ref "R18") (pin "1") (pinfunction "1_1") (pintype "passive"))
      (node (ref "U4") (pin "2") (pinfunction "TXD_2") (pintype "passive"))
    )
    (net (code "69") (name "unconnected-(CON5-Pad1)") (class "Default")
      (node (ref "CON5") (pin "1") (pinfunction "1_1") (pintype "passive"))
    )
    (net (code "70") (name "unconnected-(CON6-Pad7)") (class "Default")
      (node (ref "CON6") (pin "7") (pinfunction "7_7") (pintype "passive"))
    )
    (net (code "71") (name "unconnected-(CON6-Pad8)") (class "Default")
      (node (ref "CON6") (pin "8") (pinfunction "8_8") (pintype "passive"))
    )
    (net (code "72") (name "unconnected-(CON8-Pad1)") (class "Default")
      (node (ref "CON8") (pin "1") (pinfunction "1_1") (pintype "passive"))
    )
    (net (code "73") (name "unconnected-(CON9-Pad1)") (class "Default")
      (node (ref "CON9") (pin "1") (pinfunction "1_1") (pintype "passive"))
    )
    (net (code "74") (name "unconnected-(CON9-Pad2)") (class "Default")
      (node (ref "CON9") (pin "2") (pinfunction "2_2") (pintype "passive"))
    )
    (net (code "75") (name "unconnected-(CON10-NC-Pad2)") (class "Default")
      (node (ref "CON10") (pin "2") (pinfunction "NC_2") (pintype "passive"))
    )
    (net (code "76") (name "unconnected-(DC5V_DL-Pad3)") (class "Default")
      (node (ref "DC5V_DL") (pin "3") (pinfunction "3_3") (pintype "passive"))
    )
    (net (code "77") (name "unconnected-(DC5V_DL-Pad4)") (class "Default")
      (node (ref "DC5V_DL") (pin "4") (pinfunction "4_4") (pintype "passive"))
    )
    (net (code "78") (name "unconnected-(DC5V_DL-Pad5)") (class "Default")
      (node (ref "DC5V_DL") (pin "5") (pinfunction "5_5") (pintype "passive"))
    )
    (net (code "79") (name "unconnected-(DC5V_DL-Pad6)") (class "Default")
      (node (ref "DC5V_DL") (pin "6") (pinfunction "6_6") (pintype "passive"))
    )
    (net (code "80") (name "unconnected-(K1-Pad1)") (class "Default")
      (node (ref "K1") (pin "1") (pinfunction "1_1") (pintype "passive"))
    )
    (net (code "81") (name "unconnected-(K1-Pad2)") (class "Default")
      (node (ref "K1") (pin "2") (pinfunction "2_2") (pintype "passive"))
    )
    (net (code "82") (name "unconnected-(K2-Pad1)") (class "Default")
      (node (ref "K2") (pin "1") (pinfunction "1_1") (pintype "passive"))
    )
    (net (code "83") (name "unconnected-(K2-Pad2)") (class "Default")
      (node (ref "K2") (pin "2") (pinfunction "2_2") (pintype "passive"))
    )
    (net (code "84") (name "unconnected-(K3-Pad1)") (class "Default")
      (node (ref "K3") (pin "1") (pinfunction "1_1") (pintype "passive"))
    )
    (net (code "85") (name "unconnected-(K3-Pad2)") (class "Default")
      (node (ref "K3") (pin "2") (pinfunction "2_2") (pintype "passive"))
    )
    (net (code "86") (name "unconnected-(K4-Pad1)") (class "Default")
      (node (ref "K4") (pin "1") (pinfunction "1_1") (pintype "passive"))
    )
    (net (code "87") (name "unconnected-(K4-Pad2)") (class "Default")
      (node (ref "K4") (pin "2") (pinfunction "2_2") (pintype "passive"))
    )
    (net (code "88") (name "unconnected-(K5-Pad1)") (class "Default")
      (node (ref "K5") (pin "1") (pinfunction "1_1") (pintype "passive"))
    )
    (net (code "89") (name "unconnected-(K5-Pad2)") (class "Default")
      (node (ref "K5") (pin "2") (pinfunction "2_2") (pintype "passive"))
    )
    (net (code "90") (name "unconnected-(K6-Pad1)") (class "Default")
      (node (ref "K6") (pin "1") (pinfunction "1_1") (pintype "passive"))
    )
    (net (code "91") (name "unconnected-(K6-Pad2)") (class "Default")
      (node (ref "K6") (pin "2") (pinfunction "2_2") (pintype "passive"))
    )
    (net (code "92") (name "unconnected-(K7-Pad1)") (class "Default")
      (node (ref "K7") (pin "1") (pinfunction "1_1") (pintype "passive"))
    )
    (net (code "93") (name "unconnected-(K7-Pad2)") (class "Default")
      (node (ref "K7") (pin "2") (pinfunction "2_2") (pintype "passive"))
    )
    (net (code "94") (name "unconnected-(K8-Pad1)") (class "Default")
      (node (ref "K8") (pin "1") (pinfunction "1_1") (pintype "passive"))
    )
    (net (code "95") (name "unconnected-(K8-Pad2)") (class "Default")
      (node (ref "K8") (pin "2") (pinfunction "2_2") (pintype "passive"))
    )
    (net (code "96") (name "unconnected-(K9-Pad1)") (class "Default")
      (node (ref "K9") (pin "1") (pinfunction "1_1") (pintype "passive"))
    )
    (net (code "97") (name "unconnected-(K9-Pad2)") (class "Default")
      (node (ref "K9") (pin "2") (pinfunction "2_2") (pintype "passive"))
    )
    (net (code "98") (name "unconnected-(K10-Pad1)") (class "Default")
      (node (ref "K10") (pin "1") (pinfunction "1_1") (pintype "passive"))
    )
    (net (code "99") (name "unconnected-(K10-Pad2)") (class "Default")
      (node (ref "K10") (pin "2") (pinfunction "2_2") (pintype "passive"))
    )
    (net (code "100") (name "unconnected-(SW7-Pad1)") (class "Default")
      (node (ref "SW7") (pin "1") (pinfunction "1_1") (pintype "passive"))
    )
    (net (code "101") (name "unconnected-(SW7-Pad4)") (class "Default")
      (node (ref "SW7") (pin "4") (pinfunction "4_4") (pintype "passive"))
    )
    (net (code "102") (name "unconnected-(SW7-Pad5)") (class "Default")
      (node (ref "SW7") (pin "5") (pinfunction "5_5") (pintype "passive"))
    )
    (net (code "103") (name "unconnected-(U4-Pad9)") (class "Default")
      (node (ref "U4") (pin "9") (pinfunction "9_9") (pintype "passive"))
    )
    (net (code "104") (name "unconnected-(U4-Pad10)") (class "Default")
      (node (ref "U4") (pin "10") (pinfunction "10_10") (pintype "passive"))
    )
    (net (code "105") (name "unconnected-(U4-Pad11)") (class "Default")
      (node (ref "U4") (pin "11") (pinfunction "11_11") (pintype "passive"))
    )
    (net (code "106") (name "unconnected-(U4-Pad12)") (class "Default")
      (node (ref "U4") (pin "12") (pinfunction "12_12") (pintype "passive"))
    )
    (net (code "107") (name "unconnected-(U4-Pad13)") (class "Default")
      (node (ref "U4") (pin "13") (pinfunction "13_13") (pintype "passive"))
    )
    (net (code "108") (name "unconnected-(U4-Pad14)") (class "Default")
      (node (ref "U4") (pin "14") (pinfunction "14_14") (pintype "passive"))
    )
    (net (code "109") (name "unconnected-(U4-Pad15)") (class "Default")
      (node (ref "U4") (pin "15") (pinfunction "15_15") (pintype "passive"))
    )
  )
)
